# led-er-breakout-single.net
KiCad netlist of a schematic drawn in EAGLE
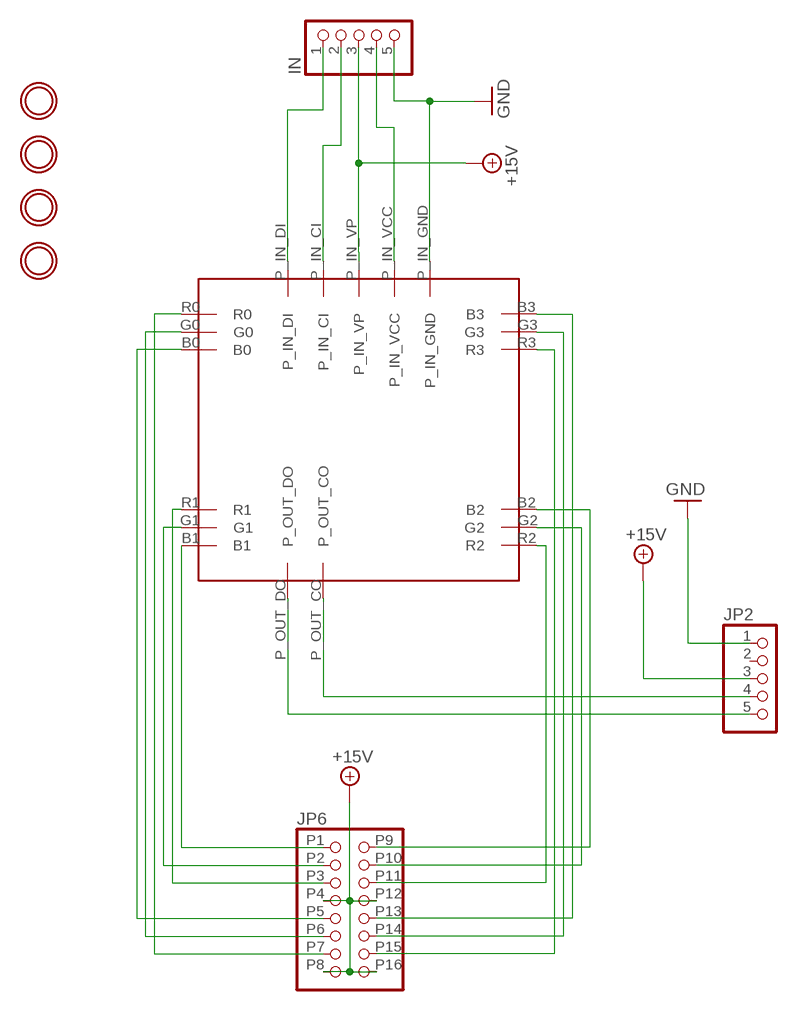
[diagram p0: schematic, sheet 1]

(export (version "E")
  (design (tool "Eeschema 10.0.6"))
  (components
    (comp (ref "IN")
      (value "HEADER-1X5")
      (footprint "eagle-import:1X05_OVAL")
      (libsource (lib "eagle-import") (part "HEADER-1X5"))
    )
    (comp (ref "JP2")
      (value "HEADER-1X5")
      (footprint "eagle-import:1X05_OVAL")
      (libsource (lib "eagle-import") (part "HEADER-1X5"))
    )
    (comp (ref "JP6")
      (value "HEADER-2X8")
      (footprint "eagle-import:2X08")
      (libsource (lib "eagle-import") (part "HEADER-2X8"))
    )
    (comp (ref "U$1")
      (value "MOUNTINGHOLE2.0")
      (footprint "eagle-import:MOUNTINGHOLE_2.0_PLATED")
      (libsource (lib "eagle-import") (part "MOUNTINGHOLE2.0"))
    )
    (comp (ref "U$2")
      (value "MOUNTINGHOLE2.0")
      (footprint "eagle-import:MOUNTINGHOLE_2.0_PLATED")
      (libsource (lib "eagle-import") (part "MOUNTINGHOLE2.0"))
    )
    (comp (ref "U$3")
      (value "MOUNTINGHOLE2.0")
      (footprint "eagle-import:MOUNTINGHOLE_2.0_PLATED")
      (libsource (lib "eagle-import") (part "MOUNTINGHOLE2.0"))
    )
    (comp (ref "U$4")
      (value "MOUNTINGHOLE2.0")
      (footprint "eagle-import:MOUNTINGHOLE_2.0_PLATED")
      (libsource (lib "eagle-import") (part "MOUNTINGHOLE2.0"))
    )
    (comp (ref "U$6")
      (value "TLC59711_BREAKOUT")
      (footprint "eagle-import:TLC59711_BREAKOUT")
      (libsource (lib "eagle-import") (part "TLC59711_BREAKOUT"))
    )
  )
  (nets
    (net (code "1") (name "+15V") (class "Default")
      (node (ref "IN") (pin "3") (pinfunction "3_3") (pintype "passive"))
      (node (ref "JP2") (pin "3") (pinfunction "3_3") (pintype "passive"))
      (node (ref "JP6") (pin "P12") (pinfunction "P12_P12") (pintype "passive"))
      (node (ref "JP6") (pin "P16") (pinfunction "P16_P16") (pintype "passive"))
      (node (ref "JP6") (pin "P4") (pinfunction "P4_P4") (pintype "passive"))
      (node (ref "JP6") (pin "P8") (pinfunction "P8_P8") (pintype "passive"))
      (node (ref "U$6") (pin "P_IN_VP") (pinfunction "P_IN_VP_P_IN_VP") (pintype "bidirectional"))
    )
    (net (code "2") (name "GND") (class "Default")
      (node (ref "IN") (pin "5") (pinfunction "5_5") (pintype "passive"))
      (node (ref "JP2") (pin "1") (pinfunction "1_1") (pintype "passive"))
      (node (ref "U$6") (pin "P_IN_GND") (pinfunction "P_IN_GND_P_IN_GND") (pintype "bidirectional"))
    )
    (net (code "3") (name "Net-(IN-Pad1)") (class "Default")
      (node (ref "IN") (pin "1") (pinfunction "1_1") (pintype "passive"))
      (node (ref "U$6") (pin "P_IN_DI") (pinfunction "P_IN_DI_P_IN_DI") (pintype "bidirectional"))
    )
    (net (code "4") (name "Net-(IN-Pad2)") (class "Default")
      (node (ref "IN") (pin "2") (pinfunction "2_2") (pintype "passive"))
      (node (ref "U$6") (pin "P_IN_CI") (pinfunction "P_IN_CI_P_IN_CI") (pintype "bidirectional"))
    )
    (net (code "5") (name "Net-(IN-Pad4)") (class "Default")
      (node (ref "IN") (pin "4") (pinfunction "4_4") (pintype "passive"))
      (node (ref "U$6") (pin "P_IN_VCC") (pinfunction "P_IN_VCC_P_IN_VCC") (pintype "bidirectional"))
    )
    (net (code "6") (name "Net-(JP2-Pad4)") (class "Default")
      (node (ref "JP2") (pin "4") (pinfunction "4_4") (pintype "passive"))
      (node (ref "U$6") (pin "P_OUT_CO") (pinfunction "P_OUT_CO_P_OUT_CO") (pintype "bidirectional"))
    )
    (net (code "7") (name "Net-(JP2-Pad5)") (class "Default")
      (node (ref "JP2") (pin "5") (pinfunction "5_5") (pintype "passive"))
      (node (ref "U$6") (pin "P_OUT_DO") (pinfunction "P_OUT_DO_P_OUT_DO") (pintype "bidirectional"))
    )
    (net (code "8") (name "Net-(JP6-PadP1)") (class "Default")
      (node (ref "JP6") (pin "P1") (pinfunction "P1_P1") (pintype "passive"))
      (node (ref "U$6") (pin "B1") (pinfunction "B1_B1") (pintype "bidirectional"))
    )
    (net (code "9") (name "Net-(JP6-PadP2)") (class "Default")
      (node (ref "JP6") (pin "P2") (pinfunction "P2_P2") (pintype "passive"))
      (node (ref "U$6") (pin "G1") (pinfunction "G1_G1") (pintype "bidirectional"))
    )
    (net (code "10") (name "Net-(JP6-PadP3)") (class "Default")
      (node (ref "JP6") (pin "P3") (pinfunction "P3_P3") (pintype "passive"))
      (node (ref "U$6") (pin "R1") (pinfunction "R1_R1") (pintype "bidirectional"))
    )
    (net (code "11") (name "Net-(JP6-PadP5)") (class "Default")
      (node (ref "JP6") (pin "P5") (pinfunction "P5_P5") (pintype "passive"))
      (node (ref "U$6") (pin "B0") (pinfunction "B0_B0") (pintype "bidirectional"))
    )
    (net (code "12") (name "Net-(JP6-PadP6)") (class "Default")
      (node (ref "JP6") (pin "P6") (pinfunction "P6_P6") (pintype "passive"))
      (node (ref "U$6") (pin "G0") (pinfunction "G0_G0") (pintype "bidirectional"))
    )
    (net (code "13") (name "Net-(JP6-PadP7)") (class "Default")
      (node (ref "JP6") (pin "P7") (pinfunction "P7_P7") (pintype "passive"))
      (node (ref "U$6") (pin "R0") (pinfunction "R0_R0") (pintype "bidirectional"))
    )
    (net (code "14") (name "Net-(JP6-PadP9)") (class "Default")
      (node (ref "JP6") (pin "P9") (pinfunction "P9_P9") (pintype "passive"))
      (node (ref "U$6") (pin "B2") (pinfunction "B2_B2") (pintype "bidirectional"))
    )
    (net (code "15") (name "Net-(JP6-PadP10)") (class "Default")
      (node (ref "JP6") (pin "P10") (pinfunction "P10_P10") (pintype "passive"))
      (node (ref "U$6") (pin "G2") (pinfunction "G2_G2") (pintype "bidirectional"))
    )
    (net (code "16") (name "Net-(JP6-PadP11)") (class "Default")
      (node (ref "JP6") (pin "P11") (pinfunction "P11_P11") (pintype "passive"))
      (node (ref "U$6") (pin "R2") (pinfunction "R2_R2") (pintype "bidirectional"))
    )
    (net (code "17") (name "Net-(JP6-PadP13)") (class "Default")
      (node (ref "JP6") (pin "P13") (pinfunction "P13_P13") (pintype "passive"))
      (node (ref "U$6") (pin "B3") (pinfunction "B3_B3") (pintype "bidirectional"))
    )
    (net (code "18") (name "Net-(JP6-PadP14)") (class "Default")
      (node (ref "JP6") (pin "P14") (pinfunction "P14_P14") (pintype "passive"))
      (node (ref "U$6") (pin "G3") (pinfunction "G3_G3") (pintype "bidirectional"))
    )
    (net (code "19") (name "Net-(JP6-PadP15)") (class "Default")
      (node (ref "JP6") (pin "P15") (pinfunction "P15_P15") (pintype "passive"))
      (node (ref "U$6") (pin "R3") (pinfunction "R3_R3") (pintype "bidirectional"))
    )
    (net (code "20") (name "unconnected-(JP2-Pad2)") (class "Default")
      (node (ref "JP2") (pin "2") (pinfunction "2_2") (pintype "passive"))
    )
  )
)
